# CX60-24S-UNIT.net
KiCad netlist of a schematic drawn in EAGLE
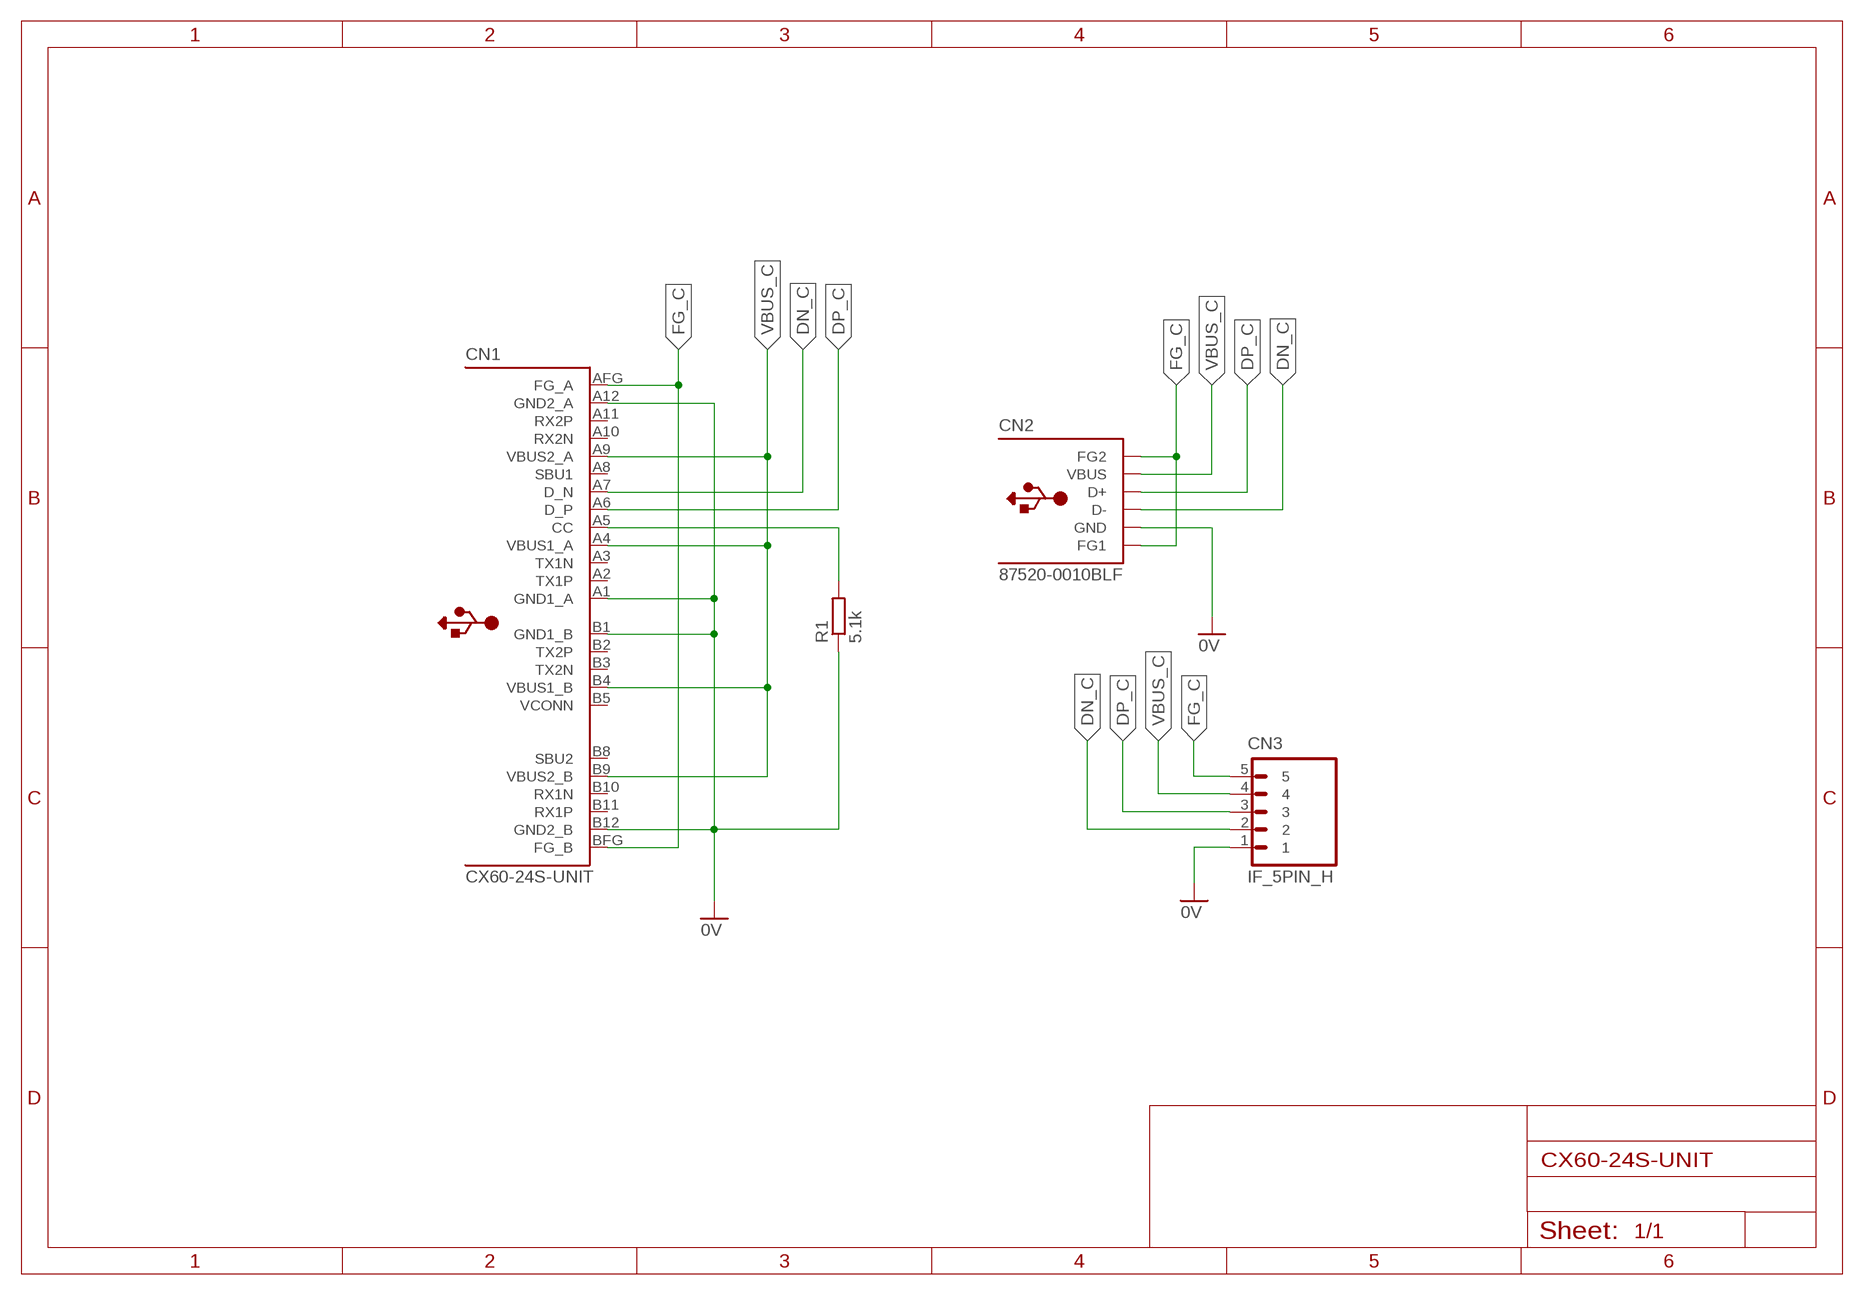
[diagram p0: schematic, sheet 1]

(export (version "E")
  (design (tool "Eeschema 10.0.6"))
  (components
    (comp (ref "CN1")
      (value "CX60-24S-UNIT")
      (footprint "eagle-import:CX60-24S-UNIT")
      (libsource (lib "eagle-import") (part "CX60-24S-UNIT"))
    )
    (comp (ref "CN2")
      (value "87520-0010BLF")
      (footprint "eagle-import:87520-0010BLF")
      (libsource (lib "eagle-import") (part "87520-0010BLF"))
    )
    (comp (ref "CN3")
      (value "IF_5PIN_H")
      (footprint "eagle-import:HEADER_5PIN")
      (libsource (lib "eagle-import") (part "IF_5PIN_H"))
    )
    (comp (ref "R1")
      (value "5.1k")
      (footprint "eagle-import:R0402")
      (libsource (lib "eagle-import") (part "RESISTOR_0402"))
    )
  )
  (nets
    (net (code "1") (name "0V") (class "Default")
      (node (ref "CN1") (pin "A1") (pinfunction "GND1_A_A1") (pintype "passive"))
      (node (ref "CN1") (pin "A12") (pinfunction "GND2_A_A12") (pintype "bidirectional"))
      (node (ref "CN1") (pin "B1") (pinfunction "GND1_B_B1") (pintype "passive"))
      (node (ref "CN1") (pin "B12") (pinfunction "GND2_B_B12") (pintype "passive"))
      (node (ref "CN2") (pin "GND") (pinfunction "GND_GND") (pintype "passive"))
      (node (ref "CN3") (pin "1") (pinfunction "1_1") (pintype "passive"))
      (node (ref "R1") (pin "1") (pinfunction "1_1") (pintype "passive"))
    )
    (net (code "2") (name "DN_C") (class "Default")
      (node (ref "CN1") (pin "A7") (pinfunction "D_N_A7") (pintype "bidirectional"))
      (node (ref "CN2") (pin "D-") (pinfunction "D-_D-") (pintype "bidirectional"))
      (node (ref "CN3") (pin "2") (pinfunction "2_2") (pintype "passive"))
    )
    (net (code "3") (name "DP_C") (class "Default")
      (node (ref "CN1") (pin "A6") (pinfunction "D_P_A6") (pintype "bidirectional"))
      (node (ref "CN2") (pin "D+") (pinfunction "D+_D+") (pintype "bidirectional"))
      (node (ref "CN3") (pin "3") (pinfunction "3_3") (pintype "passive"))
    )
    (net (code "4") (name "FG_C") (class "Default")
      (node (ref "CN1") (pin "AFG") (pinfunction "FG_A_AFG") (pintype "passive"))
      (node (ref "CN1") (pin "BFG") (pinfunction "FG_B_BFG") (pintype "passive"))
      (node (ref "CN2") (pin "FG1") (pinfunction "FG1_FG1") (pintype "passive"))
      (node (ref "CN2") (pin "FG2") (pinfunction "FG2_FG2") (pintype "passive"))
      (node (ref "CN3") (pin "5") (pinfunction "5_5") (pintype "passive"))
    )
    (net (code "5") (name "Net-(CN1-CC)") (class "Default")
      (node (ref "CN1") (pin "A5") (pinfunction "CC_A5") (pintype "passive"))
      (node (ref "R1") (pin "2") (pinfunction "2_2") (pintype "passive"))
    )
    (net (code "6") (name "VBUS_C") (class "Default")
      (node (ref "CN1") (pin "A4") (pinfunction "VBUS1_A_A4") (pintype "passive"))
      (node (ref "CN1") (pin "A9") (pinfunction "VBUS2_A_A9") (pintype "passive"))
      (node (ref "CN1") (pin "B4") (pinfunction "VBUS1_B_B4") (pintype "passive"))
      (node (ref "CN1") (pin "B9") (pinfunction "VBUS2_B_B9") (pintype "passive"))
      (node (ref "CN2") (pin "VBUS") (pinfunction "VBUS_VBUS") (pintype "passive"))
      (node (ref "CN3") (pin "4") (pinfunction "4_4") (pintype "passive"))
    )
    (net (code "7") (name "unconnected-(CN1-RX1N-PadB10)") (class "Default")
      (node (ref "CN1") (pin "B10") (pinfunction "RX1N_B10") (pintype "bidirectional"))
    )
    (net (code "8") (name "unconnected-(CN1-RX1P-PadB11)") (class "Default")
      (node (ref "CN1") (pin "B11") (pinfunction "RX1P_B11") (pintype "bidirectional"))
    )
    (net (code "9") (name "unconnected-(CN1-RX2N-PadA10)") (class "Default")
      (node (ref "CN1") (pin "A10") (pinfunction "RX2N_A10") (pintype "passive"))
    )
    (net (code "10") (name "unconnected-(CN1-RX2P-PadA11)") (class "Default")
      (node (ref "CN1") (pin "A11") (pinfunction "RX2P_A11") (pintype "bidirectional"))
    )
    (net (code "11") (name "unconnected-(CN1-SBU1-PadA8)") (class "Default")
      (node (ref "CN1") (pin "A8") (pinfunction "SBU1_A8") (pintype "passive"))
    )
    (net (code "12") (name "unconnected-(CN1-SBU2-PadB8)") (class "Default")
      (node (ref "CN1") (pin "B8") (pinfunction "SBU2_B8") (pintype "passive"))
    )
    (net (code "13") (name "unconnected-(CN1-TX1N-PadA3)") (class "Default")
      (node (ref "CN1") (pin "A3") (pinfunction "TX1N_A3") (pintype "bidirectional"))
    )
    (net (code "14") (name "unconnected-(CN1-TX1P-PadA2)") (class "Default")
      (node (ref "CN1") (pin "A2") (pinfunction "TX1P_A2") (pintype "bidirectional"))
    )
    (net (code "15") (name "unconnected-(CN1-TX2N-PadB3)") (class "Default")
      (node (ref "CN1") (pin "B3") (pinfunction "TX2N_B3") (pintype "bidirectional"))
    )
    (net (code "16") (name "unconnected-(CN1-TX2P-PadB2)") (class "Default")
      (node (ref "CN1") (pin "B2") (pinfunction "TX2P_B2") (pintype "bidirectional"))
    )
    (net (code "17") (name "unconnected-(CN1-VCONN-PadB5)") (class "Default")
      (node (ref "CN1") (pin "B5") (pinfunction "VCONN_B5") (pintype "passive"))
    )
  )
)
